# heart.net
KiCad netlist of a schematic drawn in EAGLE
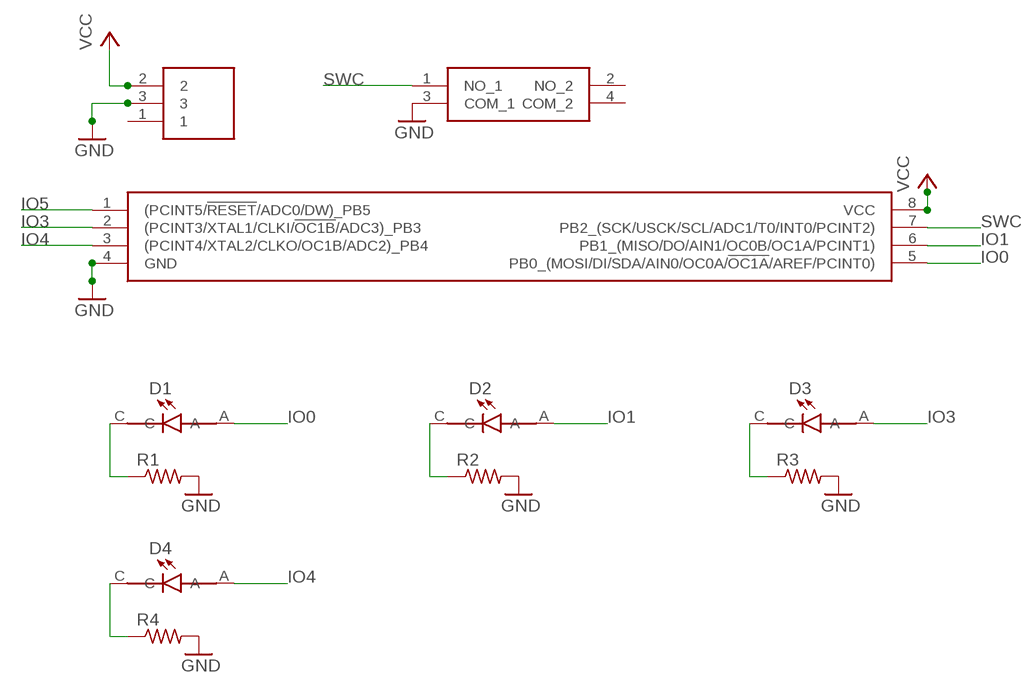
[diagram p0: schematic, sheet 1]

(export (version "E")
  (design (tool "Eeschema 10.0.6"))
  (components
    (comp (ref "D1")
      (value "SML-LXT0805IW-TR")
      (footprint "eagle-import:LEDC2012X120N")
      (fields (field (name "MF") "Lumex Opto/Components"))
      (libsource (lib "eagle-import") (part "SML-LXT0805IW-TR"))
    )
    (comp (ref "D2")
      (value "SML-LXT0805IW-TR")
      (footprint "eagle-import:LEDC2012X120N")
      (fields (field (name "MF") "Lumex Opto/Components"))
      (libsource (lib "eagle-import") (part "SML-LXT0805IW-TR"))
    )
    (comp (ref "D3")
      (value "SML-LXT0805IW-TR")
      (footprint "eagle-import:LEDC2012X120N")
      (fields (field (name "MF") "Lumex Opto/Components"))
      (libsource (lib "eagle-import") (part "SML-LXT0805IW-TR"))
    )
    (comp (ref "D4")
      (value "SML-LXT0805IW-TR")
      (footprint "eagle-import:LEDC2012X120N")
      (fields (field (name "MF") "Lumex Opto/Components"))
      (libsource (lib "eagle-import") (part "SML-LXT0805IW-TR"))
    )
    (comp (ref "IC1")
      (value "ATTINY85-20SU")
      (footprint "eagle-import:SOIC127P798X216-8N")
      (fields (field (name "MOUSER_PART_NUMBER") "556-ATTINY85-20SU"))
      (libsource (lib "eagle-import") (part "ATTINY85-20SU"))
    )
    (comp (ref "R1")
      (value "R-US_R0805")
      (footprint "eagle-import:R0805")
      (libsource (lib "eagle-import") (part "R-US_R0805"))
    )
    (comp (ref "R2")
      (value "R-US_R0805")
      (footprint "eagle-import:R0805")
      (libsource (lib "eagle-import") (part "R-US_R0805"))
    )
    (comp (ref "R3")
      (value "R-US_R0805")
      (footprint "eagle-import:R0805")
      (libsource (lib "eagle-import") (part "R-US_R0805"))
    )
    (comp (ref "R4")
      (value "R-US_R0805")
      (footprint "eagle-import:R0805")
      (libsource (lib "eagle-import") (part "R-US_R0805"))
    )
    (comp (ref "S1")
      (value "TS18-5-20-SL-160-SMT-TR")
      (footprint "eagle-import:TS18520SL160SMTTR")
      (fields (field (name "MOUSER_PART_NUMBER") "179-TS18520SL160SMTT"))
      (libsource (lib "eagle-import") (part "TS18-5-20-SL-160-SMT-TR"))
    )
    (comp (ref "U1")
      (value "BAT-HLD-001")
      (footprint "eagle-import:BATHLD001")
      (fields (field (name "MOUSER_PART_NUMBER") "712-BAT-HLD-001"))
      (libsource (lib "eagle-import") (part "BAT-HLD-001"))
    )
  )
  (nets
    (net (code "1") (name "/IO0") (class "Default")
      (node (ref "D1") (pin "A") (pinfunction "A_A") (pintype "passive"))
      (node (ref "IC1") (pin "5") (pinfunction "PB0_(MOSI/DI/SDA/AIN0/OC0A/~{OC1A}/AREF/PCINT0)_5") (pintype "bidirectional"))
    )
    (net (code "2") (name "/IO1") (class "Default")
      (node (ref "D2") (pin "A") (pinfunction "A_A") (pintype "passive"))
      (node (ref "IC1") (pin "6") (pinfunction "PB1_(MISO/DO/AIN1/OC0B/OC1A/PCINT1)_6") (pintype "bidirectional"))
    )
    (net (code "3") (name "/IO3") (class "Default")
      (node (ref "D3") (pin "A") (pinfunction "A_A") (pintype "passive"))
      (node (ref "IC1") (pin "2") (pinfunction "(PCINT3/XTAL1/CLKI/~{OC1B}/ADC3)_PB3_2") (pintype "bidirectional"))
    )
    (net (code "4") (name "/IO4") (class "Default")
      (node (ref "D4") (pin "A") (pinfunction "A_A") (pintype "passive"))
      (node (ref "IC1") (pin "3") (pinfunction "(PCINT4/XTAL2/CLKO/OC1B/ADC2)_PB4_3") (pintype "bidirectional"))
    )
    (net (code "5") (name "/IO5") (class "Default")
      (node (ref "IC1") (pin "1") (pinfunction "(PCINT5/~{RESET}/ADC0/DW)_PB5_1") (pintype "bidirectional"))
    )
    (net (code "6") (name "/SWC") (class "Default")
      (node (ref "IC1") (pin "7") (pinfunction "PB2_(SCK/USCK/SCL/ADC1/T0/INT0/PCINT2)_7") (pintype "bidirectional"))
      (node (ref "S1") (pin "1") (pinfunction "NO_1_1") (pintype "bidirectional"))
    )
    (net (code "7") (name "GND") (class "Default")
      (node (ref "IC1") (pin "4") (pinfunction "GND_4") (pintype "bidirectional"))
      (node (ref "R1") (pin "2") (pinfunction "2_2") (pintype "passive"))
      (node (ref "R2") (pin "2") (pinfunction "2_2") (pintype "passive"))
      (node (ref "R3") (pin "2") (pinfunction "2_2") (pintype "passive"))
      (node (ref "R4") (pin "2") (pinfunction "2_2") (pintype "passive"))
      (node (ref "S1") (pin "3") (pinfunction "COM_1_3") (pintype "bidirectional"))
      (node (ref "U1") (pin "3") (pinfunction "3_3") (pintype "bidirectional"))
    )
    (net (code "8") (name "Net-(D1-PadC)") (class "Default")
      (node (ref "D1") (pin "C") (pinfunction "C_C") (pintype "passive"))
      (node (ref "R1") (pin "1") (pinfunction "1_1") (pintype "passive"))
    )
    (net (code "9") (name "Net-(D2-PadC)") (class "Default")
      (node (ref "D2") (pin "C") (pinfunction "C_C") (pintype "passive"))
      (node (ref "R2") (pin "1") (pinfunction "1_1") (pintype "passive"))
    )
    (net (code "10") (name "Net-(D3-PadC)") (class "Default")
      (node (ref "D3") (pin "C") (pinfunction "C_C") (pintype "passive"))
      (node (ref "R3") (pin "1") (pinfunction "1_1") (pintype "passive"))
    )
    (net (code "11") (name "Net-(D4-PadC)") (class "Default")
      (node (ref "D4") (pin "C") (pinfunction "C_C") (pintype "passive"))
      (node (ref "R4") (pin "1") (pinfunction "1_1") (pintype "passive"))
    )
    (net (code "12") (name "VCC") (class "Default")
      (node (ref "IC1") (pin "8") (pinfunction "VCC_8") (pintype "bidirectional"))
      (node (ref "U1") (pin "2") (pinfunction "2_2") (pintype "bidirectional"))
    )
    (net (code "13") (name "unconnected-(S1-COM_2-Pad4)") (class "Default")
      (node (ref "S1") (pin "4") (pinfunction "COM_2_4") (pintype "bidirectional"))
    )
    (net (code "14") (name "unconnected-(S1-NO_2-Pad2)") (class "Default")
      (node (ref "S1") (pin "2") (pinfunction "NO_2_2") (pintype "bidirectional"))
    )
    (net (code "15") (name "unconnected-(U1-Pad1)") (class "Default")
      (node (ref "U1") (pin "1") (pinfunction "1_1") (pintype "bidirectional"))
    )
  )
)
